# AlcoholDetectie_met_bus.net
KiCad netlist of a schematic drawn in Altium Designer
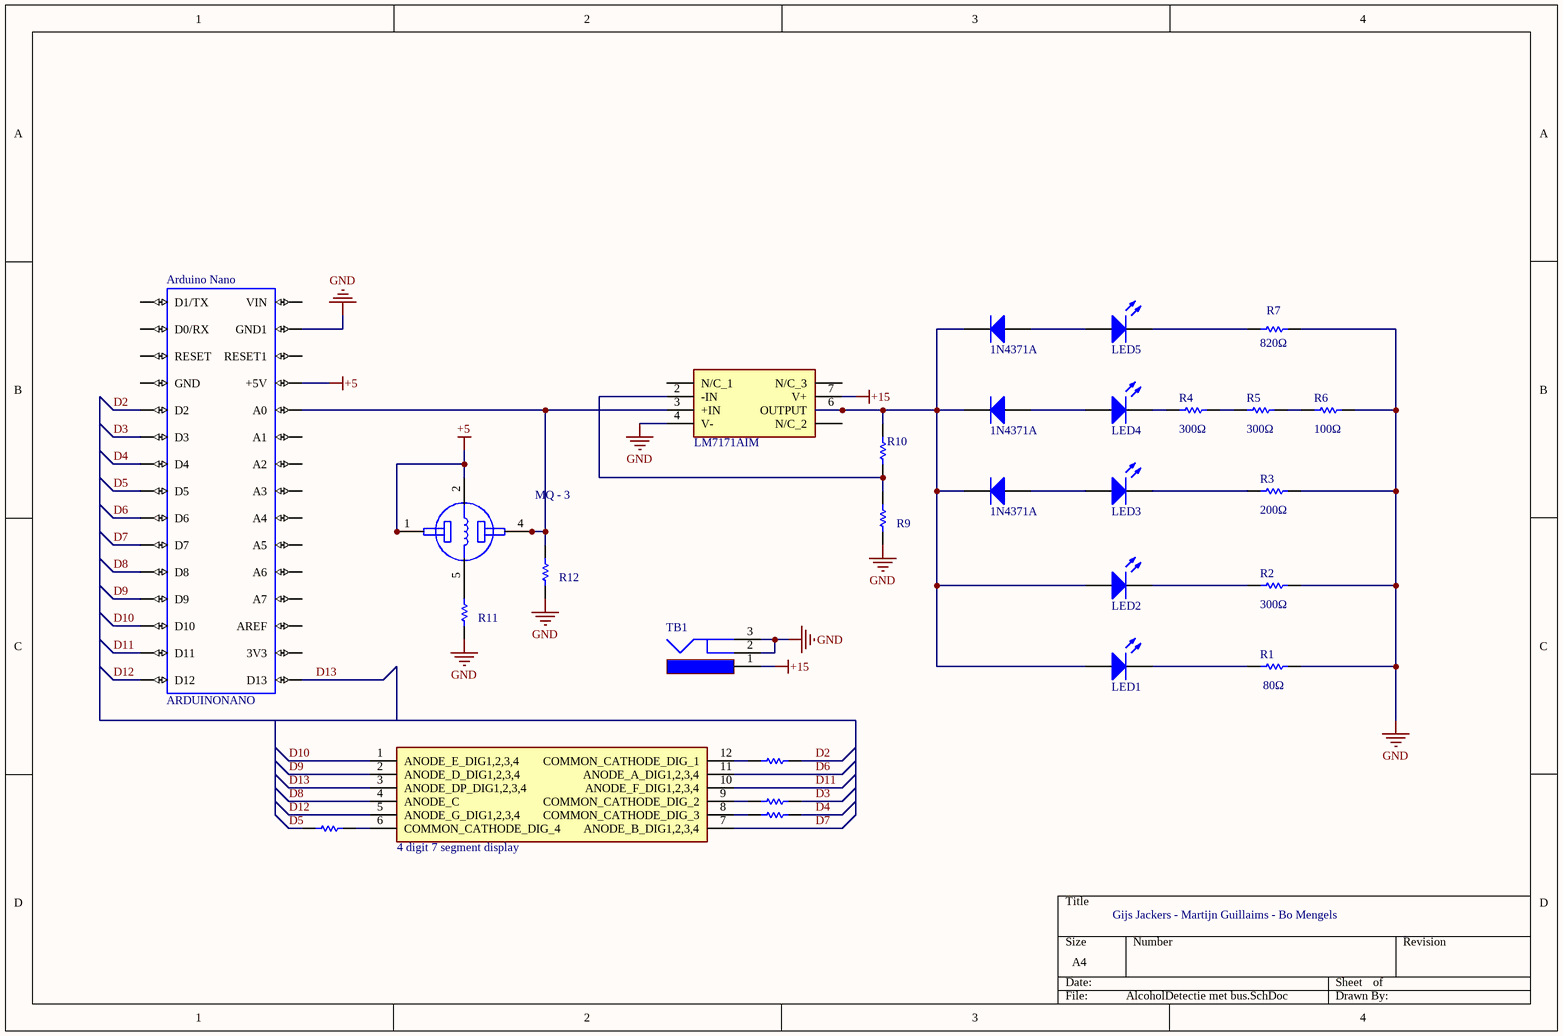
[diagram p0: AlcoholDetectie met bus.SchDoc]

(export (version "E")
  (design (tool "Eeschema 10.0.6"))
  (components
    (comp (ref "4 digit 7 segment display")
      (value "CC56-12SRWA")
      (footprint "SamacSys:CC5612SRWA")
      (description "Display")
      (fields (field (name "MOUSER2 PART NUMBER") "604-CC56-12SRWA"))
      (libsource (lib "*") (part "CC56-12SRWA"))
    )
    (comp (ref "Arduino Nano")
      (value "ARDUINONANO")
      (footprint "PDIP-32")
      (description "Arduino; 20MHz; 3.3Ã·5VDC; Flash: 32kB; SRAM: 2kB; ATMEGA328,FT232R")
      (fields (field (name "MF") "Arduino"))
      (libsource (lib "ARDUINONANO") (part "ARDUINONANO"))
    )
    (comp (ref "COMPERATOR")
      (value "LM7171AIM")
      (footprint "SamacSys:SOIC127P600X175-8N")
      (description "Integrated Circuit")
      (fields
        (field (name "MOUSER2 PART NUMBER") "926-LM7171AIMX/NOPB")
        (field (name "MANUFACTURER_PART_NUMBER") "LM7171AIMX/NOPB")
      )
      (libsource (lib "*") (part "LM7171AIMX_NOPB"))
    )
    (comp (ref "D1")
      (value "1N4371A")
      (footprint "DO-35")
      (description "High Conductance Fast Diode")
      (fields (field (name "PUBLISHER") "Altium Limited"))
      (libsource (lib "Miscellaneous Devices") (part "Diode 1N4148"))
    )
    (comp (ref "D2")
      (value "1N4371A")
      (footprint "DO-35")
      (description "High Conductance Fast Diode")
      (fields (field (name "PUBLISHER") "Altium Limited"))
      (libsource (lib "Miscellaneous Devices") (part "Diode 1N4148"))
    )
    (comp (ref "D3")
      (value "1N4371A")
      (footprint "DO-35")
      (description "High Conductance Fast Diode")
      (fields (field (name "PUBLISHER") "Altium Limited"))
      (libsource (lib "Miscellaneous Devices") (part "Diode 1N4148"))
    )
    (comp (ref "GROEN")
      (value "LED1")
      (footprint "LED-1")
      (description "Typical RED GaAs LED")
      (fields (field (name "PUBLISHER") "Altium Limited"))
      (libsource (lib "Miscellaneous Devices") (part "LED1"))
    )
    (comp (ref "MQ - 3")
      (value "SEN-08880")
      (footprint "XDCR_SEN-08880")
      (description "Alcohol _C2H6O_ Sensor 0 V ~ 3.3 V")
      (fields (field (name "MF") "SparkFun Electronics"))
      (libsource (lib "SEN-08880") (part "SEN-08880"))
    )
    (comp (ref "ORANJE_1")
      (value "LED2")
      (footprint "LED-1")
      (description "Typical RED GaAs LED")
      (fields (field (name "PUBLISHER") "Altium Limited"))
      (libsource (lib "Miscellaneous Devices") (part "LED1"))
    )
    (comp (ref "ORANJE_2")
      (value "LED3")
      (footprint "LED-1")
      (description "Typical RED GaAs LED")
      (fields (field (name "PUBLISHER") "Altium Limited"))
      (libsource (lib "Miscellaneous Devices") (part "LED1"))
    )
    (comp (ref "R1")
      (value "80Ω")
      (footprint "RESC2013X50X30LL20T20")
      (fields (field (name "MANUFACTURER") "Vishay Dale") (field (name "PART NUMBER") "CRCW08050000Z0EA"))
      (libsource (lib "Altium Content Vault") (part "RES"))
    )
    (comp (ref "R2")
      (value "300Ω")
      (footprint "RESC2013X50X30LL20T20")
      (fields (field (name "MANUFACTURER") "Vishay Dale") (field (name "PART NUMBER") "CRCW08050000Z0EA"))
      (libsource (lib "Altium Content Vault") (part "RES"))
    )
    (comp (ref "R3")
      (value "200Ω")
      (footprint "RESC2013X50X30LL20T20")
      (fields (field (name "MANUFACTURER") "Vishay Dale") (field (name "PART NUMBER") "CRCW08050000Z0EA"))
      (libsource (lib "Altium Content Vault") (part "RES"))
    )
    (comp (ref "R4")
      (value "300Ω")
      (footprint "RESC2013X50X30LL20T20")
      (fields (field (name "MANUFACTURER") "Vishay Dale") (field (name "PART NUMBER") "CRCW08050000Z0EA"))
      (libsource (lib "Altium Content Vault") (part "RES"))
    )
    (comp (ref "R5")
      (value "300Ω")
      (footprint "RESC2013X50X30LL20T20")
      (fields (field (name "MANUFACTURER") "Vishay Dale") (field (name "PART NUMBER") "CRCW08050000Z0EA"))
      (libsource (lib "Altium Content Vault") (part "RES"))
    )
    (comp (ref "R6")
      (value "100Ω")
      (footprint "RESC2013X50X30LL20T20")
      (fields (field (name "MANUFACTURER") "Vishay Dale") (field (name "PART NUMBER") "CRCW08050000Z0EA"))
      (libsource (lib "Altium Content Vault") (part "RES"))
    )
    (comp (ref "R7")
      (value "820Ω")
      (footprint "RESC2013X50X30LL20T20")
      (fields (field (name "MANUFACTURER") "Vishay Dale") (field (name "PART NUMBER") "CRCW08050000Z0EA"))
      (libsource (lib "Altium Content Vault") (part "RES"))
    )
    (comp (ref "R9")
      (value "1k Ω")
      (footprint "RESC2013X50X30LL20T20")
      (fields (field (name "MANUFACTURER") "Vishay Dale") (field (name "PART NUMBER") "CRCW08050000Z0EA"))
      (libsource (lib "Altium Content Vault") (part "RES"))
    )
    (comp (ref "R10")
      (value "1k Ω")
      (footprint "RESC2013X50X30LL20T20")
      (fields (field (name "MANUFACTURER") "Vishay Dale") (field (name "PART NUMBER") "CRCW08050000Z0EA"))
      (libsource (lib "Altium Content Vault") (part "RES"))
    )
    (comp (ref "R11")
      (value "5,1 Ω")
      (footprint "RESC2013X50X30LL20T20")
      (fields (field (name "MANUFACTURER") "Vishay Dale") (field (name "PART NUMBER") "CRCW08050000Z0EA"))
      (libsource (lib "Altium Content Vault") (part "RES"))
    )
    (comp (ref "R12")
      (value "1k Ω")
      (footprint "RESC2013X50X30LL20T20")
      (fields (field (name "MANUFACTURER") "Vishay Dale") (field (name "PART NUMBER") "CRCW08050000Z0EA"))
      (libsource (lib "Altium Content Vault") (part "RES"))
    )
    (comp (ref "R13")
      (value "330 Ω")
      (footprint "RESC2013X50X30LL20T20")
      (fields (field (name "MANUFACTURER") "Vishay Dale") (field (name "PART NUMBER") "CRCW08050000Z0EA"))
      (libsource (lib "Altium Content Vault") (part "RES"))
    )
    (comp (ref "R14")
      (value "330 Ω")
      (footprint "RESC2013X50X30LL20T20")
      (fields (field (name "MANUFACTURER") "Vishay Dale") (field (name "PART NUMBER") "CRCW08050000Z0EA"))
      (libsource (lib "Altium Content Vault") (part "RES"))
    )
    (comp (ref "R15")
      (value "330 Ω")
      (footprint "RESC2013X50X30LL20T20")
      (fields (field (name "MANUFACTURER") "Vishay Dale") (field (name "PART NUMBER") "CRCW08050000Z0EA"))
      (libsource (lib "Altium Content Vault") (part "RES"))
    )
    (comp (ref "R16")
      (value "330 Ω")
      (footprint "RESC2013X50X30LL20T20")
      (fields (field (name "MANUFACTURER") "Vishay Dale") (field (name "PART NUMBER") "CRCW08050000Z0EA"))
      (libsource (lib "Altium Content Vault") (part "RES"))
    )
    (comp (ref "ROOD_1")
      (value "LED4")
      (footprint "LED-1")
      (description "Typical RED GaAs LED")
      (fields (field (name "PUBLISHER") "Altium Limited"))
      (libsource (lib "Miscellaneous Devices") (part "LED1"))
    )
    (comp (ref "ROOD_2")
      (value "LED5")
      (footprint "LED-1")
      (description "Typical RED GaAs LED")
      (fields (field (name "PUBLISHER") "Altium Limited"))
      (libsource (lib "Miscellaneous Devices") (part "LED1"))
    )
    (comp (ref "TB1")
      (value "Component_1")
      (footprint "MJ-180PH")
      (libsource (lib "TB1") (part "Component_1"))
    )
  )
  (nets
    (net (code "1") (name "+5") (class "Default")
      (node (ref "Arduino Nano") (pin "+5V") (pinfunction "+5V_+5V") (pintype "bidirectional"))
      (node (ref "MQ - 3") (pin "1") (pinfunction "A_1") (pintype "passive"))
      (node (ref "MQ - 3") (pin "2") (pinfunction "H1_2") (pintype "passive"))
      (node (ref "MQ - 3") (pin "3") (pinfunction "A_3") (pintype "passive"))
    )
    (net (code "2") (name "+15") (class "Default")
      (node (ref "COMPERATOR") (pin "7") (pinfunction "V+_7") (pintype "passive"))
      (node (ref "TB1") (pin "1") (pinfunction "1_1") (pintype "passive"))
    )
    (net (code "3") (name "/D2") (class "Default")
      (node (ref "Arduino Nano") (pin "D2") (pinfunction "D2_D2") (pintype "bidirectional"))
      (node (ref "R14") (pin "1") (pinfunction "1_1") (pintype "passive"))
    )
    (net (code "4") (name "/D3") (class "Default")
      (node (ref "Arduino Nano") (pin "D3") (pinfunction "D3_D3") (pintype "bidirectional"))
      (node (ref "R15") (pin "1") (pinfunction "1_1") (pintype "passive"))
    )
    (net (code "5") (name "/D4") (class "Default")
      (node (ref "Arduino Nano") (pin "D4") (pinfunction "D4_D4") (pintype "bidirectional"))
      (node (ref "R16") (pin "1") (pinfunction "1_1") (pintype "passive"))
    )
    (net (code "6") (name "/D5") (class "Default")
      (node (ref "Arduino Nano") (pin "D5") (pinfunction "D5_D5") (pintype "bidirectional"))
      (node (ref "R13") (pin "2") (pinfunction "2_2") (pintype "passive"))
    )
    (net (code "7") (name "/D6") (class "Default")
      (node (ref "4 digit 7 segment display") (pin "11") (pinfunction "ANODE_A_DIG1,2,3,4_11") (pintype "passive"))
      (node (ref "Arduino Nano") (pin "D6") (pinfunction "D6_D6") (pintype "bidirectional"))
    )
    (net (code "8") (name "/D7") (class "Default")
      (node (ref "4 digit 7 segment display") (pin "7") (pinfunction "ANODE_B_DIG1,2,3,4_7") (pintype "passive"))
      (node (ref "Arduino Nano") (pin "D7") (pinfunction "D7_D7") (pintype "bidirectional"))
    )
    (net (code "9") (name "/D8") (class "Default")
      (node (ref "4 digit 7 segment display") (pin "4") (pinfunction "ANODE_C_4") (pintype "passive"))
      (node (ref "Arduino Nano") (pin "D8") (pinfunction "D8_D8") (pintype "bidirectional"))
    )
    (net (code "10") (name "/D9") (class "Default")
      (node (ref "4 digit 7 segment display") (pin "2") (pinfunction "ANODE_D_DIG1,2,3,4_2") (pintype "passive"))
      (node (ref "Arduino Nano") (pin "D9") (pinfunction "D9_D9") (pintype "bidirectional"))
    )
    (net (code "11") (name "/D10") (class "Default")
      (node (ref "4 digit 7 segment display") (pin "1") (pinfunction "ANODE_E_DIG1,2,3,4_1") (pintype "passive"))
      (node (ref "Arduino Nano") (pin "D10") (pinfunction "D10_D10") (pintype "bidirectional"))
    )
    (net (code "12") (name "/D11") (class "Default")
      (node (ref "4 digit 7 segment display") (pin "10") (pinfunction "ANODE_F_DIG1,2,3,4_10") (pintype "passive"))
      (node (ref "Arduino Nano") (pin "D11") (pinfunction "D11_D11") (pintype "bidirectional"))
    )
    (net (code "13") (name "/D12") (class "Default")
      (node (ref "4 digit 7 segment display") (pin "5") (pinfunction "ANODE_G_DIG1,2,3,4_5") (pintype "passive"))
      (node (ref "Arduino Nano") (pin "D12") (pinfunction "D12_D12") (pintype "bidirectional"))
    )
    (net (code "14") (name "/D13") (class "Default")
      (node (ref "4 digit 7 segment display") (pin "3") (pinfunction "ANODE_DP_DIG1,2,3,4_3") (pintype "passive"))
      (node (ref "Arduino Nano") (pin "D13") (pinfunction "D13_D13") (pintype "bidirectional"))
    )
    (net (code "15") (name "GND") (class "Default")
      (node (ref "Arduino Nano") (pin "GND1") (pinfunction "GND1_GND1") (pintype "bidirectional"))
      (node (ref "COMPERATOR") (pin "4") (pinfunction "V-_4") (pintype "passive"))
      (node (ref "R1") (pin "2") (pinfunction "2_2") (pintype "passive"))
      (node (ref "R11") (pin "1") (pinfunction "1_1") (pintype "passive"))
      (node (ref "R12") (pin "1") (pinfunction "1_1") (pintype "passive"))
      (node (ref "R2") (pin "2") (pinfunction "2_2") (pintype "passive"))
      (node (ref "R3") (pin "2") (pinfunction "2_2") (pintype "passive"))
      (node (ref "R6") (pin "2") (pinfunction "2_2") (pintype "passive"))
      (node (ref "R7") (pin "2") (pinfunction "2_2") (pintype "passive"))
      (node (ref "R9") (pin "1") (pinfunction "1_1") (pintype "passive"))
      (node (ref "TB1") (pin "2") (pinfunction "2_2") (pintype "passive"))
      (node (ref "TB1") (pin "3") (pinfunction "3_3") (pintype "passive"))
    )
    (net (code "16") (name "Net-(4 digit 7 segment display-COMMON_CATHODE_DIG_1)") (class "Default")
      (node (ref "4 digit 7 segment display") (pin "12") (pinfunction "COMMON_CATHODE_DIG_1_12") (pintype "passive"))
      (node (ref "R14") (pin "2") (pinfunction "2_2") (pintype "passive"))
    )
    (net (code "17") (name "Net-(4 digit 7 segment display-COMMON_CATHODE_DIG_2)") (class "Default")
      (node (ref "4 digit 7 segment display") (pin "9") (pinfunction "COMMON_CATHODE_DIG_2_9") (pintype "passive"))
      (node (ref "R15") (pin "2") (pinfunction "2_2") (pintype "passive"))
    )
    (net (code "18") (name "Net-(4 digit 7 segment display-COMMON_CATHODE_DIG_3)") (class "Default")
      (node (ref "4 digit 7 segment display") (pin "8") (pinfunction "COMMON_CATHODE_DIG_3_8") (pintype "passive"))
      (node (ref "R16") (pin "2") (pinfunction "2_2") (pintype "passive"))
    )
    (net (code "19") (name "Net-(4 digit 7 segment display-COMMON_CATHODE_DIG_4)") (class "Default")
      (node (ref "4 digit 7 segment display") (pin "6") (pinfunction "COMMON_CATHODE_DIG_4_6") (pintype "passive"))
      (node (ref "R13") (pin "1") (pinfunction "1_1") (pintype "passive"))
    )
    (net (code "20") (name "Net-(COMPERATOR-+IN)") (class "Default")
      (node (ref "Arduino Nano") (pin "A0") (pinfunction "A0_A0") (pintype "bidirectional"))
      (node (ref "COMPERATOR") (pin "3") (pinfunction "+IN_3") (pintype "passive"))
      (node (ref "MQ - 3") (pin "4") (pinfunction "B_4") (pintype "passive"))
      (node (ref "MQ - 3") (pin "6") (pinfunction "B_6") (pintype "passive"))
      (node (ref "R12") (pin "2") (pinfunction "2_2") (pintype "passive"))
    )
    (net (code "21") (name "Net-(COMPERATOR--IN)") (class "Default")
      (node (ref "COMPERATOR") (pin "2") (pinfunction "-IN_2") (pintype "passive"))
      (node (ref "R10") (pin "1") (pinfunction "1_1") (pintype "passive"))
      (node (ref "R9") (pin "2") (pinfunction "2_2") (pintype "passive"))
    )
    (net (code "22") (name "Net-(COMPERATOR-OUTPUT)") (class "Default")
      (node (ref "COMPERATOR") (pin "6") (pinfunction "OUTPUT_6") (pintype "passive"))
      (node (ref "D1") (pin "2") (pinfunction "K_2") (pintype "passive"))
      (node (ref "D2") (pin "2") (pinfunction "K_2") (pintype "passive"))
      (node (ref "D3") (pin "2") (pinfunction "K_2") (pintype "passive"))
      (node (ref "GROEN") (pin "1") (pinfunction "A_1") (pintype "passive"))
      (node (ref "ORANJE_1") (pin "1") (pinfunction "A_1") (pintype "passive"))
      (node (ref "R10") (pin "2") (pinfunction "2_2") (pintype "passive"))
    )
    (net (code "23") (name "Net-(D1-A)") (class "Default")
      (node (ref "D1") (pin "1") (pinfunction "A_1") (pintype "passive"))
      (node (ref "ORANJE_2") (pin "1") (pinfunction "A_1") (pintype "passive"))
    )
    (net (code "24") (name "Net-(D2-A)") (class "Default")
      (node (ref "D2") (pin "1") (pinfunction "A_1") (pintype "passive"))
      (node (ref "ROOD_1") (pin "1") (pinfunction "A_1") (pintype "passive"))
    )
    (net (code "25") (name "Net-(D3-A)") (class "Default")
      (node (ref "D3") (pin "1") (pinfunction "A_1") (pintype "passive"))
      (node (ref "ROOD_2") (pin "1") (pinfunction "A_1") (pintype "passive"))
    )
    (net (code "26") (name "Net-(GROEN-K)") (class "Default")
      (node (ref "GROEN") (pin "2") (pinfunction "K_2") (pintype "passive"))
      (node (ref "R1") (pin "1") (pinfunction "1_1") (pintype "passive"))
    )
    (net (code "27") (name "Net-(MQ - 3-H2)") (class "Default")
      (node (ref "MQ - 3") (pin "5") (pinfunction "H2_5") (pintype "passive"))
      (node (ref "R11") (pin "2") (pinfunction "2_2") (pintype "passive"))
    )
    (net (code "28") (name "Net-(ORANJE_1-K)") (class "Default")
      (node (ref "ORANJE_1") (pin "2") (pinfunction "K_2") (pintype "passive"))
      (node (ref "R2") (pin "1") (pinfunction "1_1") (pintype "passive"))
    )
    (net (code "29") (name "Net-(ORANJE_2-K)") (class "Default")
      (node (ref "ORANJE_2") (pin "2") (pinfunction "K_2") (pintype "passive"))
      (node (ref "R3") (pin "1") (pinfunction "1_1") (pintype "passive"))
    )
    (net (code "30") (name "Net-(R4-Pad2)") (class "Default")
      (node (ref "R4") (pin "2") (pinfunction "2_2") (pintype "passive"))
      (node (ref "R5") (pin "1") (pinfunction "1_1") (pintype "passive"))
    )
    (net (code "31") (name "Net-(R5-Pad2)") (class "Default")
      (node (ref "R5") (pin "2") (pinfunction "2_2") (pintype "passive"))
      (node (ref "R6") (pin "1") (pinfunction "1_1") (pintype "passive"))
    )
    (net (code "32") (name "Net-(ROOD_1-K)") (class "Default")
      (node (ref "R4") (pin "1") (pinfunction "1_1") (pintype "passive"))
      (node (ref "ROOD_1") (pin "2") (pinfunction "K_2") (pintype "passive"))
    )
    (net (code "33") (name "Net-(ROOD_2-K)") (class "Default")
      (node (ref "R7") (pin "1") (pinfunction "1_1") (pintype "passive"))
      (node (ref "ROOD_2") (pin "2") (pinfunction "K_2") (pintype "passive"))
    )
    (net (code "34") (name "unconnected-(Arduino Nano-Pad3V3)") (class "Default")
      (node (ref "Arduino Nano") (pin "3V3") (pinfunction "3V3_3V3") (pintype "bidirectional"))
    )
    (net (code "35") (name "unconnected-(Arduino Nano-PadA1)") (class "Default")
      (node (ref "Arduino Nano") (pin "A1") (pinfunction "A1_A1") (pintype "bidirectional"))
    )
    (net (code "36") (name "unconnected-(Arduino Nano-PadA2)") (class "Default")
      (node (ref "Arduino Nano") (pin "A2") (pinfunction "A2_A2") (pintype "bidirectional"))
    )
    (net (code "37") (name "unconnected-(Arduino Nano-PadA3)") (class "Default")
      (node (ref "Arduino Nano") (pin "A3") (pinfunction "A3_A3") (pintype "bidirectional"))
    )
    (net (code "38") (name "unconnected-(Arduino Nano-PadA4)") (class "Default")
      (node (ref "Arduino Nano") (pin "A4") (pinfunction "A4_A4") (pintype "bidirectional"))
    )
    (net (code "39") (name "unconnected-(Arduino Nano-PadA5)") (class "Default")
      (node (ref "Arduino Nano") (pin "A5") (pinfunction "A5_A5") (pintype "bidirectional"))
    )
    (net (code "40") (name "unconnected-(Arduino Nano-PadA6)") (class "Default")
      (node (ref "Arduino Nano") (pin "A6") (pinfunction "A6_A6") (pintype "bidirectional"))
    )
    (net (code "41") (name "unconnected-(Arduino Nano-PadA7)") (class "Default")
      (node (ref "Arduino Nano") (pin "A7") (pinfunction "A7_A7") (pintype "bidirectional"))
    )
    (net (code "42") (name "unconnected-(Arduino Nano-PadAREF)") (class "Default")
      (node (ref "Arduino Nano") (pin "AREF") (pinfunction "AREF_AREF") (pintype "bidirectional"))
    )
    (net (code "43") (name "unconnected-(Arduino Nano-PadD0{slash}RX)") (class "Default")
      (node (ref "Arduino Nano") (pin "D0/RX") (pinfunction "D0/RX_D0/RX") (pintype "bidirectional"))
    )
    (net (code "44") (name "unconnected-(Arduino Nano-PadD1{slash}TX)") (class "Default")
      (node (ref "Arduino Nano") (pin "D1/TX") (pinfunction "D1/TX_D1/TX") (pintype "bidirectional"))
    )
    (net (code "45") (name "unconnected-(Arduino Nano-PadGND)") (class "Default")
      (node (ref "Arduino Nano") (pin "GND") (pinfunction "GND_GND") (pintype "bidirectional"))
    )
    (net (code "46") (name "unconnected-(Arduino Nano-PadRESET)") (class "Default")
      (node (ref "Arduino Nano") (pin "RESET") (pinfunction "RESET_RESET") (pintype "bidirectional"))
    )
    (net (code "47") (name "unconnected-(Arduino Nano-PadRESET1)") (class "Default")
      (node (ref "Arduino Nano") (pin "RESET1") (pinfunction "RESET1_RESET1") (pintype "bidirectional"))
    )
    (net (code "48") (name "unconnected-(Arduino Nano-PadVIN)") (class "Default")
      (node (ref "Arduino Nano") (pin "VIN") (pinfunction "VIN_VIN") (pintype "bidirectional"))
    )
    (net (code "49") (name "unconnected-(COMPERATOR-N{slash}C_1-Pad1)") (class "Default")
      (node (ref "COMPERATOR") (pin "1") (pinfunction "N/C_1_1") (pintype "passive"))
    )
    (net (code "50") (name "unconnected-(COMPERATOR-N{slash}C_2-Pad5)") (class "Default")
      (node (ref "COMPERATOR") (pin "5") (pinfunction "N/C_2_5") (pintype "passive"))
    )
    (net (code "51") (name "unconnected-(COMPERATOR-N{slash}C_3-Pad8)") (class "Default")
      (node (ref "COMPERATOR") (pin "8") (pinfunction "N/C_3_8") (pintype "passive"))
    )
  )
)
